# EKSR_Instrument_Rev_B.net
KiCad netlist of a schematic drawn in EAGLE
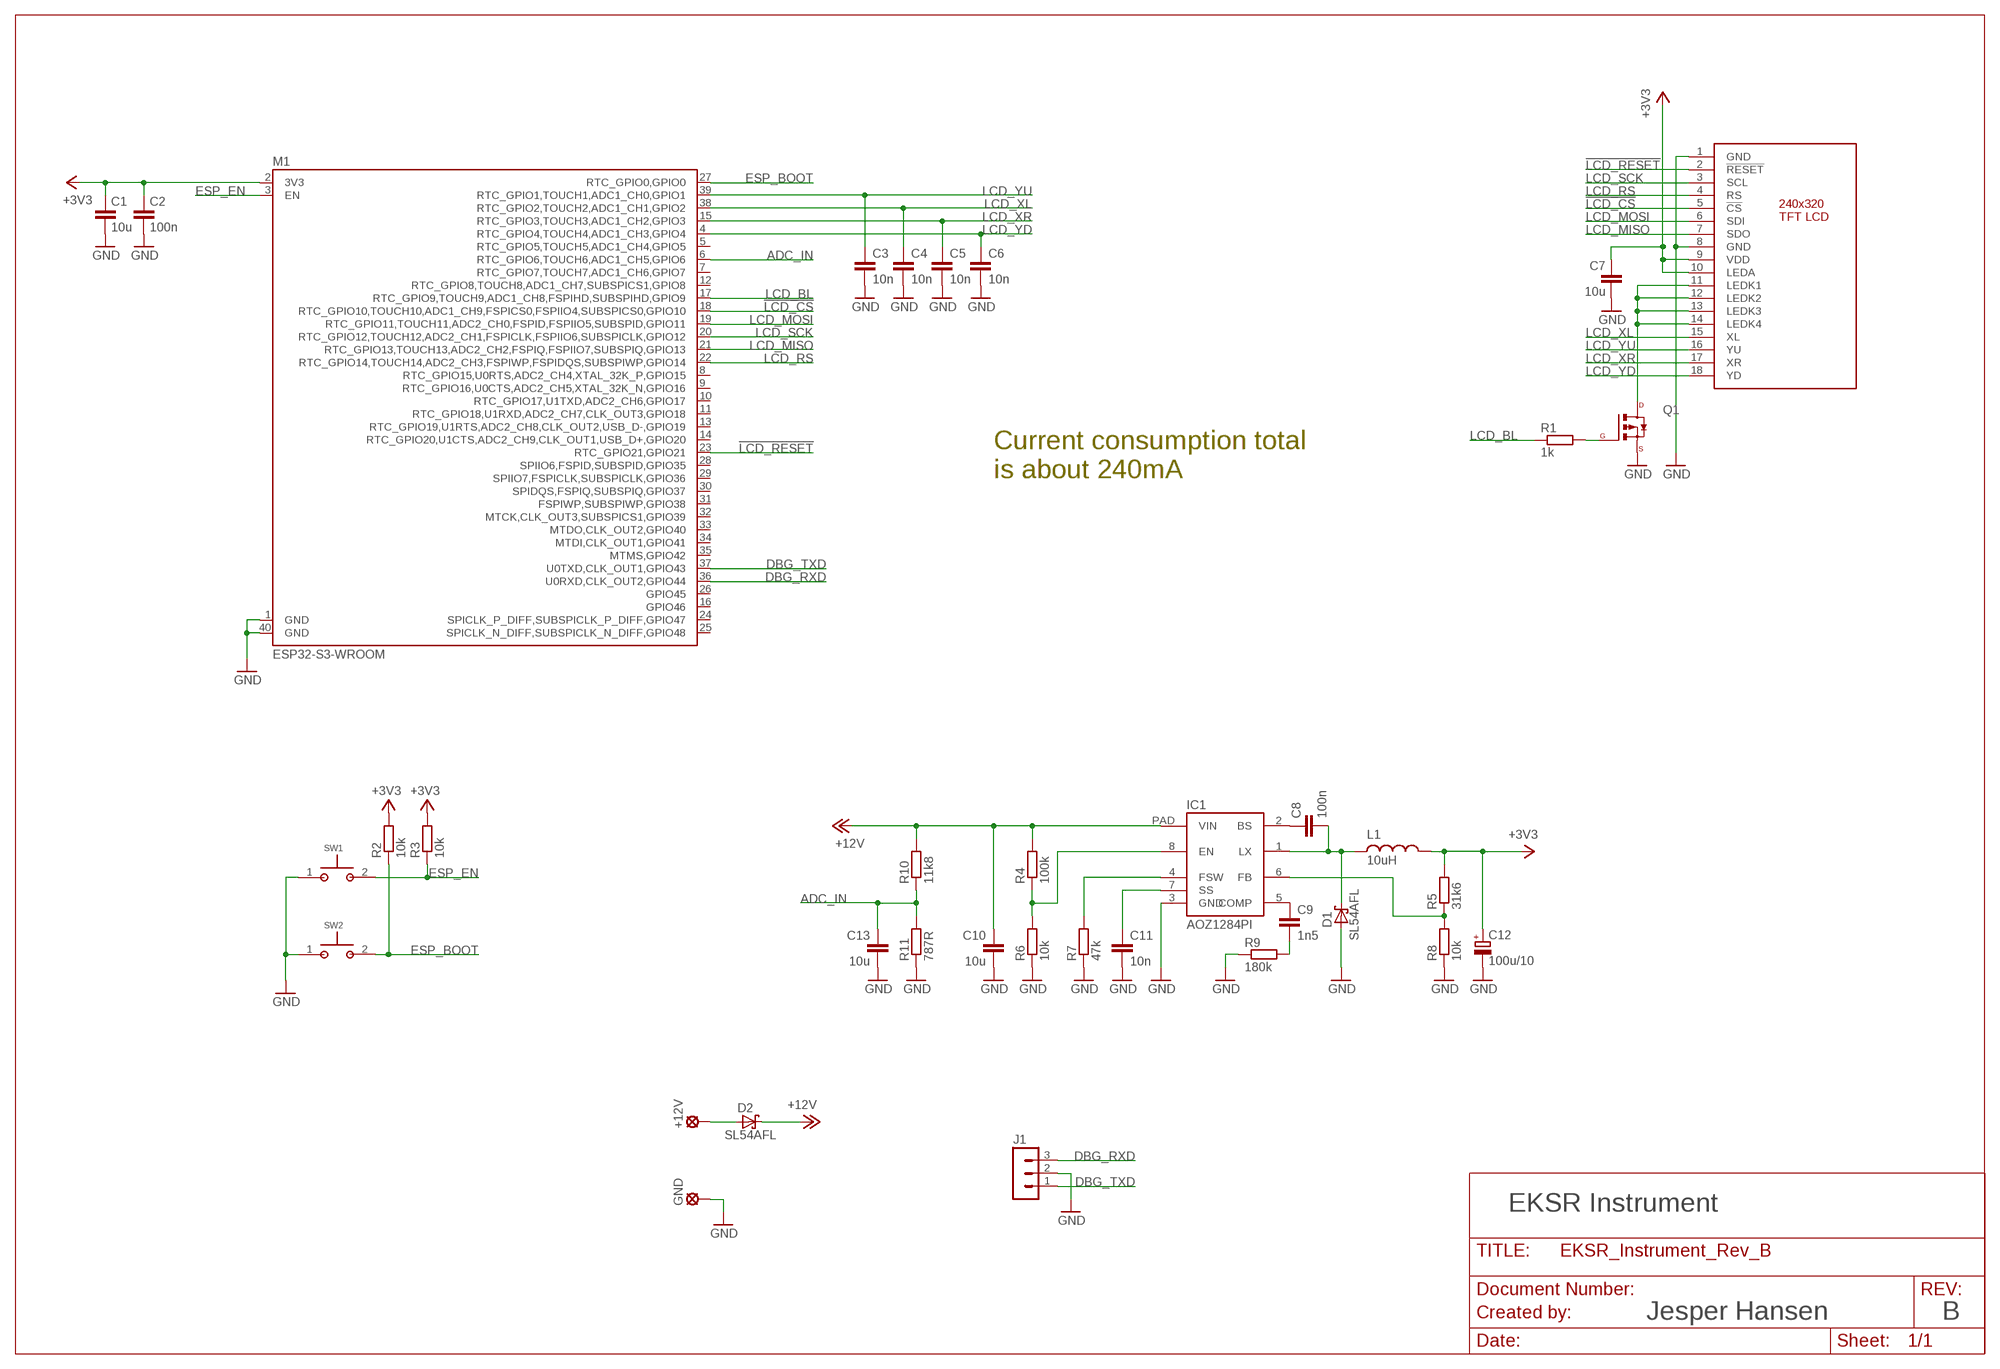
[diagram p0: schematic, sheet 1]

(export (version "E")
  (design (tool "Eeschema 10.0.6"))
  (components
    (comp (ref "+12V")
      (value "LSP13")
      (footprint "eagle-import:LSP13")
      (libsource (lib "eagle-import") (part "LSP13"))
    )
    (comp (ref "C1")
      (value "10u")
      (footprint "eagle-import:C0603")
      (libsource (lib "eagle-import") (part "CC0603"))
    )
    (comp (ref "C2")
      (value "100n")
      (footprint "eagle-import:C0603")
      (libsource (lib "eagle-import") (part "CC0603"))
    )
    (comp (ref "C3")
      (value "10n")
      (footprint "eagle-import:C0603")
      (libsource (lib "eagle-import") (part "CC0603"))
    )
    (comp (ref "C4")
      (value "10n")
      (footprint "eagle-import:C0603")
      (libsource (lib "eagle-import") (part "CC0603"))
    )
    (comp (ref "C5")
      (value "10n")
      (footprint "eagle-import:C0603")
      (libsource (lib "eagle-import") (part "CC0603"))
    )
    (comp (ref "C6")
      (value "10n")
      (footprint "eagle-import:C0603")
      (libsource (lib "eagle-import") (part "CC0603"))
    )
    (comp (ref "C7")
      (value "10u")
      (footprint "eagle-import:C0603")
      (libsource (lib "eagle-import") (part "CC0603"))
    )
    (comp (ref "C8")
      (value "100n")
      (footprint "eagle-import:C0603")
      (libsource (lib "eagle-import") (part "CC0603"))
    )
    (comp (ref "C9")
      (value "1n5")
      (footprint "eagle-import:C0603")
      (libsource (lib "eagle-import") (part "CC0603"))
    )
    (comp (ref "C10")
      (value "10u")
      (footprint "eagle-import:C0603")
      (libsource (lib "eagle-import") (part "CC0603"))
    )
    (comp (ref "C11")
      (value "10n")
      (footprint "eagle-import:C0603")
      (libsource (lib "eagle-import") (part "CC0603"))
    )
    (comp (ref "C12")
      (value "100u/10")
      (footprint "eagle-import:CT3528")
      (libsource (lib "eagle-import") (part "CPOLCT3528"))
    )
    (comp (ref "C13")
      (value "10u")
      (footprint "eagle-import:C0603")
      (libsource (lib "eagle-import") (part "CC0603"))
    )
    (comp (ref "D1")
      (value "SL54AFL")
      (footprint "eagle-import:DO221-AC")
      (libsource (lib "eagle-import") (part "SCHOTTKY"))
    )
    (comp (ref "D2")
      (value "SL54AFL")
      (footprint "eagle-import:DO221-AC")
      (libsource (lib "eagle-import") (part "SCHOTTKY"))
    )
    (comp (ref "DISP1")
      (value "TFT_2.4_A\"")
      (footprint "eagle-import:TFT_2.4_A2")
      (libsource (lib "eagle-import") (part "TFT_2.4_A{dblquote}"))
    )
    (comp (ref "GND")
      (value "LSP13")
      (footprint "eagle-import:LSP13")
      (libsource (lib "eagle-import") (part "LSP13"))
    )
    (comp (ref "IC1")
      (value "AOZ1284PI")
      (footprint "eagle-import:SO8_EDP")
      (libsource (lib "eagle-import") (part "AOZ1284PI"))
    )
    (comp (ref "J1")
      (value "MA03-1W")
      (footprint "eagle-import:MA03-1W")
      (libsource (lib "eagle-import") (part "MA03-1W"))
    )
    (comp (ref "L1")
      (value "10uH")
      (footprint "eagle-import:SPM6530")
      (libsource (lib "eagle-import") (part "INDUCTOR"))
    )
    (comp (ref "M1")
      (value "ESP32-S3-WROOM")
      (footprint "eagle-import:ESP32-S3-WROOM")
      (libsource (lib "eagle-import") (part "ESP32-S3-WROOM"))
    )
    (comp (ref "Q1")
      (value "MOSFET_P")
      (footprint "eagle-import:SOT-23")
      (libsource (lib "eagle-import") (part "MOSFET_P"))
    )
    (comp (ref "R1")
      (value "1k")
      (footprint "eagle-import:R0603")
      (libsource (lib "eagle-import") (part "RR0603"))
    )
    (comp (ref "R2")
      (value "10k")
      (footprint "eagle-import:R0603")
      (libsource (lib "eagle-import") (part "RR0603"))
    )
    (comp (ref "R3")
      (value "10k")
      (footprint "eagle-import:R0603")
      (libsource (lib "eagle-import") (part "RR0603"))
    )
    (comp (ref "R4")
      (value "100k")
      (footprint "eagle-import:R0603")
      (libsource (lib "eagle-import") (part "RR0603"))
    )
    (comp (ref "R5")
      (value "31k6")
      (footprint "eagle-import:R0603")
      (libsource (lib "eagle-import") (part "RR0603"))
    )
    (comp (ref "R6")
      (value "10k")
      (footprint "eagle-import:R0603")
      (libsource (lib "eagle-import") (part "RR0603"))
    )
    (comp (ref "R7")
      (value "47k")
      (footprint "eagle-import:R0603")
      (libsource (lib "eagle-import") (part "RR0603"))
    )
    (comp (ref "R8")
      (value "10k")
      (footprint "eagle-import:R0603")
      (libsource (lib "eagle-import") (part "RR0603"))
    )
    (comp (ref "R9")
      (value "180k")
      (footprint "eagle-import:R0603")
      (libsource (lib "eagle-import") (part "RR0603"))
    )
    (comp (ref "R10")
      (value "11k8")
      (footprint "eagle-import:R0603")
      (libsource (lib "eagle-import") (part "RR0603"))
    )
    (comp (ref "R11")
      (value "787R")
      (footprint "eagle-import:R0603")
      (libsource (lib "eagle-import") (part "RR0603"))
    )
    (comp (ref "SW1")
      (value "PTS820")
      (footprint "eagle-import:PTS820")
      (libsource (lib "eagle-import") (part "PTS820"))
    )
    (comp (ref "SW2")
      (value "PTS820")
      (footprint "eagle-import:PTS820")
      (libsource (lib "eagle-import") (part "PTS820"))
    )
  )
  (nets
    (net (code "1") (name "+3V3") (class "Default")
      (node (ref "C1") (pin "1") (pinfunction "1_1") (pintype "passive"))
      (node (ref "C12") (pin "+") (pinfunction "+_+") (pintype "passive"))
      (node (ref "C2") (pin "1") (pinfunction "1_1") (pintype "passive"))
      (node (ref "C7") (pin "1") (pinfunction "1_1") (pintype "passive"))
      (node (ref "DISP1") (pin "10") (pinfunction "LEDA_10") (pintype "passive"))
      (node (ref "DISP1") (pin "9") (pinfunction "VDD_9") (pintype "power_in"))
      (node (ref "L1") (pin "2") (pinfunction "P$2_2") (pintype "passive"))
      (node (ref "M1") (pin "2") (pinfunction "3V3_2") (pintype "power_in"))
      (node (ref "R2") (pin "2") (pinfunction "2_2") (pintype "passive"))
      (node (ref "R3") (pin "2") (pinfunction "2_2") (pintype "passive"))
      (node (ref "R5") (pin "2") (pinfunction "2_2") (pintype "passive"))
    )
    (net (code "2") (name "+12V") (class "Default")
      (node (ref "C10") (pin "1") (pinfunction "1_1") (pintype "passive"))
      (node (ref "D2") (pin "C") (pinfunction "C_C") (pintype "passive"))
      (node (ref "IC1") (pin "PAD") (pinfunction "VIN_PAD") (pintype "power_in"))
      (node (ref "R10") (pin "2") (pinfunction "2_2") (pintype "passive"))
      (node (ref "R4") (pin "2") (pinfunction "2_2") (pintype "passive"))
    )
    (net (code "3") (name "/ADC_IN") (class "Default")
      (node (ref "C13") (pin "1") (pinfunction "1_1") (pintype "passive"))
      (node (ref "M1") (pin "6") (pinfunction "RTC_GPIO6,TOUCH6,ADC1_CH5,GPIO6_6") (pintype "bidirectional"))
      (node (ref "R10") (pin "1") (pinfunction "1_1") (pintype "passive"))
      (node (ref "R11") (pin "2") (pinfunction "2_2") (pintype "passive"))
    )
    (net (code "4") (name "/DBG_RXD") (class "Default")
      (node (ref "J1") (pin "3") (pinfunction "3_3") (pintype "passive"))
      (node (ref "M1") (pin "36") (pinfunction "U0RXD,CLK_OUT2,GPIO44_36") (pintype "input"))
    )
    (net (code "5") (name "/DBG_TXD") (class "Default")
      (node (ref "J1") (pin "1") (pinfunction "1_1") (pintype "passive"))
      (node (ref "M1") (pin "37") (pinfunction "U0TXD,CLK_OUT1,GPIO43_37") (pintype "input"))
    )
    (net (code "6") (name "/ESP_BOOT") (class "Default")
      (node (ref "M1") (pin "27") (pinfunction "RTC_GPIO0,GPIO0_27") (pintype "bidirectional"))
      (node (ref "R2") (pin "1") (pinfunction "1_1") (pintype "passive"))
      (node (ref "SW2") (pin "2") (pinfunction "P$2_2") (pintype "passive"))
    )
    (net (code "7") (name "/ESP_EN") (class "Default")
      (node (ref "M1") (pin "3") (pinfunction "EN_3") (pintype "input"))
      (node (ref "R3") (pin "1") (pinfunction "1_1") (pintype "passive"))
      (node (ref "SW1") (pin "2") (pinfunction "P$2_2") (pintype "passive"))
    )
    (net (code "8") (name "/LCD_BL") (class "Default")
      (node (ref "M1") (pin "17") (pinfunction "RTC_GPIO9,TOUCH9,ADC1_CH8,FSPIHD,SUBSPIHD,GPIO9_17") (pintype "bidirectional"))
      (node (ref "R1") (pin "1") (pinfunction "1_1") (pintype "passive"))
    )
    (net (code "9") (name "/LCD_MISO") (class "Default")
      (node (ref "DISP1") (pin "7") (pinfunction "SDO_7") (pintype "bidirectional"))
      (node (ref "M1") (pin "21") (pinfunction "RTC_GPIO13,TOUCH13,ADC2_CH2,FSPIQ,FSPIIO7,SUBSPIQ,GPIO13_21") (pintype "bidirectional"))
    )
    (net (code "10") (name "/LCD_MOSI") (class "Default")
      (node (ref "DISP1") (pin "6") (pinfunction "SDI_6") (pintype "input"))
      (node (ref "M1") (pin "19") (pinfunction "RTC_GPIO11,TOUCH11,ADC2_CH0,FSPID,FSPIIO5,SUBSPID,GPIO11_19") (pintype "bidirectional"))
    )
    (net (code "11") (name "/LCD_RS") (class "Default")
      (node (ref "DISP1") (pin "4") (pinfunction "RS_4") (pintype "input"))
      (node (ref "M1") (pin "22") (pinfunction "RTC_GPIO14,TOUCH14,ADC2_CH3,FSPIWP,FSPIDQS,SUBSPIWP,GPIO14_22") (pintype "bidirectional"))
    )
    (net (code "12") (name "/LCD_SCK") (class "Default")
      (node (ref "DISP1") (pin "3") (pinfunction "SCL_3") (pintype "input"))
      (node (ref "M1") (pin "20") (pinfunction "RTC_GPIO12,TOUCH12,ADC2_CH1,FSPICLK,FSPIIO6,SUBSPICLK,GPIO12_20") (pintype "bidirectional"))
    )
    (net (code "13") (name "/LCD_XL") (class "Default")
      (node (ref "C4") (pin "1") (pinfunction "1_1") (pintype "passive"))
      (node (ref "DISP1") (pin "15") (pinfunction "XL_15") (pintype "passive"))
      (node (ref "M1") (pin "38") (pinfunction "RTC_GPIO2,TOUCH2,ADC1_CH1,GPIO2_38") (pintype "bidirectional"))
    )
    (net (code "14") (name "/LCD_XR") (class "Default")
      (node (ref "C5") (pin "1") (pinfunction "1_1") (pintype "passive"))
      (node (ref "DISP1") (pin "17") (pinfunction "XR_17") (pintype "passive"))
      (node (ref "M1") (pin "15") (pinfunction "RTC_GPIO3,TOUCH3,ADC1_CH2,GPIO3_15") (pintype "bidirectional"))
    )
    (net (code "15") (name "/LCD_YD") (class "Default")
      (node (ref "C6") (pin "1") (pinfunction "1_1") (pintype "passive"))
      (node (ref "DISP1") (pin "18") (pinfunction "YD_18") (pintype "passive"))
      (node (ref "M1") (pin "4") (pinfunction "RTC_GPIO4,TOUCH4,ADC1_CH3,GPIO4_4") (pintype "bidirectional"))
    )
    (net (code "16") (name "/LCD_YU") (class "Default")
      (node (ref "C3") (pin "1") (pinfunction "1_1") (pintype "passive"))
      (node (ref "DISP1") (pin "16") (pinfunction "YU_16") (pintype "passive"))
      (node (ref "M1") (pin "39") (pinfunction "RTC_GPIO1,TOUCH1,ADC1_CH0,GPIO1_39") (pintype "bidirectional"))
    )
    (net (code "17") (name "/~{LCD_CS}") (class "Default")
      (node (ref "DISP1") (pin "5") (pinfunction "~{CS}_5") (pintype "input"))
      (node (ref "M1") (pin "18") (pinfunction "RTC_GPIO10,TOUCH10,ADC1_CH9,FSPICS0,FSPIIO4,SUBSPICS0,GPIO10_18") (pintype "bidirectional"))
    )
    (net (code "18") (name "/~{LCD_RESET}") (class "Default")
      (node (ref "DISP1") (pin "2") (pinfunction "~{RESET}_2") (pintype "input"))
      (node (ref "M1") (pin "23") (pinfunction "RTC_GPIO21,GPIO21_23") (pintype "bidirectional"))
    )
    (net (code "19") (name "GND") (class "Default")
      (node (ref "C1") (pin "2") (pinfunction "2_2") (pintype "passive"))
      (node (ref "C10") (pin "2") (pinfunction "2_2") (pintype "passive"))
      (node (ref "C11") (pin "2") (pinfunction "2_2") (pintype "passive"))
      (node (ref "C12") (pin "-") (pinfunction "-_-") (pintype "passive"))
      (node (ref "C13") (pin "2") (pinfunction "2_2") (pintype "passive"))
      (node (ref "C2") (pin "2") (pinfunction "2_2") (pintype "passive"))
      (node (ref "C3") (pin "2") (pinfunction "2_2") (pintype "passive"))
      (node (ref "C4") (pin "2") (pinfunction "2_2") (pintype "passive"))
      (node (ref "C5") (pin "2") (pinfunction "2_2") (pintype "passive"))
      (node (ref "C6") (pin "2") (pinfunction "2_2") (pintype "passive"))
      (node (ref "C7") (pin "2") (pinfunction "2_2") (pintype "passive"))
      (node (ref "D1") (pin "A") (pinfunction "A_A") (pintype "passive"))
      (node (ref "DISP1") (pin "1") (pinfunction "GND_1") (pintype "power_in"))
      (node (ref "DISP1") (pin "8") (pinfunction "GND_8") (pintype "power_in"))
      (node (ref "GND") (pin "MP") (pinfunction "MP_MP") (pintype "passive"))
      (node (ref "IC1") (pin "3") (pinfunction "GND_3") (pintype "power_in"))
      (node (ref "J1") (pin "2") (pinfunction "2_2") (pintype "passive"))
      (node (ref "M1") (pin "1") (pinfunction "GND_1") (pintype "power_in"))
      (node (ref "M1") (pin "40") (pinfunction "GND_40") (pintype "power_in"))
      (node (ref "Q1") (pin "2") (pinfunction "P_S_2") (pintype "passive"))
      (node (ref "R11") (pin "1") (pinfunction "1_1") (pintype "passive"))
      (node (ref "R6") (pin "1") (pinfunction "1_1") (pintype "passive"))
      (node (ref "R7") (pin "1") (pinfunction "1_1") (pintype "passive"))
      (node (ref "R8") (pin "1") (pinfunction "1_1") (pintype "passive"))
      (node (ref "R9") (pin "1") (pinfunction "1_1") (pintype "passive"))
      (node (ref "SW1") (pin "1") (pinfunction "P$1_1") (pintype "passive"))
      (node (ref "SW2") (pin "1") (pinfunction "P$1_1") (pintype "passive"))
    )
    (net (code "20") (name "Net-(+12V-PadMP)") (class "Default")
      (node (ref "+12V") (pin "MP") (pinfunction "MP_MP") (pintype "passive"))
      (node (ref "D2") (pin "A") (pinfunction "A_A") (pintype "passive"))
    )
    (net (code "21") (name "Net-(C9-Pad2)") (class "Default")
      (node (ref "C9") (pin "2") (pinfunction "2_2") (pintype "passive"))
      (node (ref "R9") (pin "2") (pinfunction "2_2") (pintype "passive"))
    )
    (net (code "22") (name "Net-(DISP1-LEDK1)") (class "Default")
      (node (ref "DISP1") (pin "11") (pinfunction "LEDK1_11") (pintype "passive"))
      (node (ref "DISP1") (pin "12") (pinfunction "LEDK2_12") (pintype "passive"))
      (node (ref "DISP1") (pin "13") (pinfunction "LEDK3_13") (pintype "passive"))
      (node (ref "DISP1") (pin "14") (pinfunction "LEDK4_14") (pintype "passive"))
      (node (ref "Q1") (pin "3") (pinfunction "P_D_3") (pintype "passive"))
    )
    (net (code "23") (name "Net-(IC1-BS)") (class "Default")
      (node (ref "C8") (pin "1") (pinfunction "1_1") (pintype "passive"))
      (node (ref "IC1") (pin "2") (pinfunction "BS_2") (pintype "passive"))
    )
    (net (code "24") (name "Net-(IC1-COMP)") (class "Default")
      (node (ref "C9") (pin "1") (pinfunction "1_1") (pintype "passive"))
      (node (ref "IC1") (pin "5") (pinfunction "COMP_5") (pintype "passive"))
    )
    (net (code "25") (name "Net-(IC1-EN)") (class "Default")
      (node (ref "IC1") (pin "8") (pinfunction "EN_8") (pintype "input"))
      (node (ref "R4") (pin "1") (pinfunction "1_1") (pintype "passive"))
      (node (ref "R6") (pin "2") (pinfunction "2_2") (pintype "passive"))
    )
    (net (code "26") (name "Net-(IC1-FB)") (class "Default")
      (node (ref "IC1") (pin "6") (pinfunction "FB_6") (pintype "input"))
      (node (ref "R5") (pin "1") (pinfunction "1_1") (pintype "passive"))
      (node (ref "R8") (pin "2") (pinfunction "2_2") (pintype "passive"))
    )
    (net (code "27") (name "Net-(IC1-FSW)") (class "Default")
      (node (ref "IC1") (pin "4") (pinfunction "FSW_4") (pintype "input"))
      (node (ref "R7") (pin "2") (pinfunction "2_2") (pintype "passive"))
    )
    (net (code "28") (name "Net-(IC1-LX)") (class "Default")
      (node (ref "C8") (pin "2") (pinfunction "2_2") (pintype "passive"))
      (node (ref "D1") (pin "C") (pinfunction "C_C") (pintype "passive"))
      (node (ref "IC1") (pin "1") (pinfunction "LX_1") (pintype "output"))
      (node (ref "L1") (pin "1") (pinfunction "P$1_1") (pintype "passive"))
    )
    (net (code "29") (name "Net-(IC1-SS)") (class "Default")
      (node (ref "C11") (pin "1") (pinfunction "1_1") (pintype "passive"))
      (node (ref "IC1") (pin "7") (pinfunction "SS_7") (pintype "passive"))
    )
    (net (code "30") (name "Net-(Q1-P_G)") (class "Default")
      (node (ref "Q1") (pin "1") (pinfunction "P_G_1") (pintype "passive"))
      (node (ref "R1") (pin "2") (pinfunction "2_2") (pintype "passive"))
    )
    (net (code "31") (name "unconnected-(M1-FSPIWP,SUBSPIWP,GPIO38-Pad31)") (class "Default")
      (node (ref "M1") (pin "31") (pinfunction "FSPIWP,SUBSPIWP,GPIO38_31") (pintype "bidirectional"))
    )
    (net (code "32") (name "unconnected-(M1-GPIO45-Pad26)") (class "Default")
      (node (ref "M1") (pin "26") (pinfunction "GPIO45_26") (pintype "input"))
    )
    (net (code "33") (name "unconnected-(M1-GPIO46-Pad16)") (class "Default")
      (node (ref "M1") (pin "16") (pinfunction "GPIO46_16") (pintype "input"))
    )
    (net (code "34") (name "unconnected-(M1-MTCK,CLK_OUT3,SUBSPICS1,GPIO39-Pad32)") (class "Default")
      (node (ref "M1") (pin "32") (pinfunction "MTCK,CLK_OUT3,SUBSPICS1,GPIO39_32") (pintype "bidirectional"))
    )
    (net (code "35") (name "unconnected-(M1-MTDI,CLK_OUT1,GPIO41-Pad34)") (class "Default")
      (node (ref "M1") (pin "34") (pinfunction "MTDI,CLK_OUT1,GPIO41_34") (pintype "input"))
    )
    (net (code "36") (name "unconnected-(M1-MTDO,CLK_OUT2,GPIO40-Pad33)") (class "Default")
      (node (ref "M1") (pin "33") (pinfunction "MTDO,CLK_OUT2,GPIO40_33") (pintype "bidirectional"))
    )
    (net (code "37") (name "unconnected-(M1-MTMS,GPIO42-Pad35)") (class "Default")
      (node (ref "M1") (pin "35") (pinfunction "MTMS,GPIO42_35") (pintype "input"))
    )
    (net (code "38") (name "unconnected-(M1-RTC_GPIO5,TOUCH5,ADC1_CH4,GPIO5-Pad5)") (class "Default")
      (node (ref "M1") (pin "5") (pinfunction "RTC_GPIO5,TOUCH5,ADC1_CH4,GPIO5_5") (pintype "bidirectional"))
    )
    (net (code "39") (name "unconnected-(M1-RTC_GPIO7,TOUCH7,ADC1_CH6,GPIO7-Pad7)") (class "Default")
      (node (ref "M1") (pin "7") (pinfunction "RTC_GPIO7,TOUCH7,ADC1_CH6,GPIO7_7") (pintype "bidirectional"))
    )
    (net (code "40") (name "unconnected-(M1-RTC_GPIO8,TOUCH8,ADC1_CH7,SUBSPICS1,GPIO8-Pad12)") (class "Default")
      (node (ref "M1") (pin "12") (pinfunction "RTC_GPIO8,TOUCH8,ADC1_CH7,SUBSPICS1,GPIO8_12") (pintype "bidirectional"))
    )
    (net (code "41") (name "unconnected-(M1-RTC_GPIO15,U0RTS,ADC2_CH4,XTAL_32K_P,GPIO15-Pad8)") (class "Default")
      (node (ref "M1") (pin "8") (pinfunction "RTC_GPIO15,U0RTS,ADC2_CH4,XTAL_32K_P,GPIO15_8") (pintype "bidirectional"))
    )
    (net (code "42") (name "unconnected-(M1-RTC_GPIO16,U0CTS,ADC2_CH5,XTAL_32K_N,GPIO16-Pad9)") (class "Default")
      (node (ref "M1") (pin "9") (pinfunction "RTC_GPIO16,U0CTS,ADC2_CH5,XTAL_32K_N,GPIO16_9") (pintype "bidirectional"))
    )
    (net (code "43") (name "unconnected-(M1-RTC_GPIO17,U1TXD,ADC2_CH6,GPIO17-Pad10)") (class "Default")
      (node (ref "M1") (pin "10") (pinfunction "RTC_GPIO17,U1TXD,ADC2_CH6,GPIO17_10") (pintype "bidirectional"))
    )
    (net (code "44") (name "unconnected-(M1-RTC_GPIO18,U1RXD,ADC2_CH7,CLK_OUT3,GPIO18-Pad11)") (class "Default")
      (node (ref "M1") (pin "11") (pinfunction "RTC_GPIO18,U1RXD,ADC2_CH7,CLK_OUT3,GPIO18_11") (pintype "bidirectional"))
    )
    (net (code "45") (name "unconnected-(M1-RTC_GPIO19,U1RTS,ADC2_CH8,CLK_OUT2,USB_D-,GPIO19-Pad13)") (class "Default")
      (node (ref "M1") (pin "13") (pinfunction "RTC_GPIO19,U1RTS,ADC2_CH8,CLK_OUT2,USB_D-,GPIO19_13") (pintype "bidirectional"))
    )
    (net (code "46") (name "unconnected-(M1-RTC_GPIO20,U1CTS,ADC2_CH9,CLK_OUT1,USB_D+,GPIO20-Pad14)") (class "Default")
      (node (ref "M1") (pin "14") (pinfunction "RTC_GPIO20,U1CTS,ADC2_CH9,CLK_OUT1,USB_D+,GPIO20_14") (pintype "bidirectional"))
    )
    (net (code "47") (name "unconnected-(M1-SPICLK_N_DIFF,SUBSPICLK_N_DIFF,GPIO48-Pad25)") (class "Default")
      (node (ref "M1") (pin "25") (pinfunction "SPICLK_N_DIFF,SUBSPICLK_N_DIFF,GPIO48_25") (pintype "input"))
    )
    (net (code "48") (name "unconnected-(M1-SPICLK_P_DIFF,SUBSPICLK_P_DIFF,GPIO47-Pad24)") (class "Default")
      (node (ref "M1") (pin "24") (pinfunction "SPICLK_P_DIFF,SUBSPICLK_P_DIFF,GPIO47_24") (pintype "input"))
    )
    (net (code "49") (name "unconnected-(M1-SPIDQS,FSPIQ,SUBSPIQ,GPIO37-Pad30)") (class "Default")
      (node (ref "M1") (pin "30") (pinfunction "SPIDQS,FSPIQ,SUBSPIQ,GPIO37_30") (pintype "bidirectional"))
    )
    (net (code "50") (name "unconnected-(M1-SPIIO6,FSPID,SUBSPID,GPIO35-Pad28)") (class "Default")
      (node (ref "M1") (pin "28") (pinfunction "SPIIO6,FSPID,SUBSPID,GPIO35_28") (pintype "bidirectional"))
    )
    (net (code "51") (name "unconnected-(M1-SPIIO7,FSPICLK,SUBSPICLK,GPIO36-Pad29)") (class "Default")
      (node (ref "M1") (pin "29") (pinfunction "SPIIO7,FSPICLK,SUBSPICLK,GPIO36_29") (pintype "bidirectional"))
    )
  )
)
